# UART_Communication.net
KiCad netlist of a schematic drawn in Altium Designer
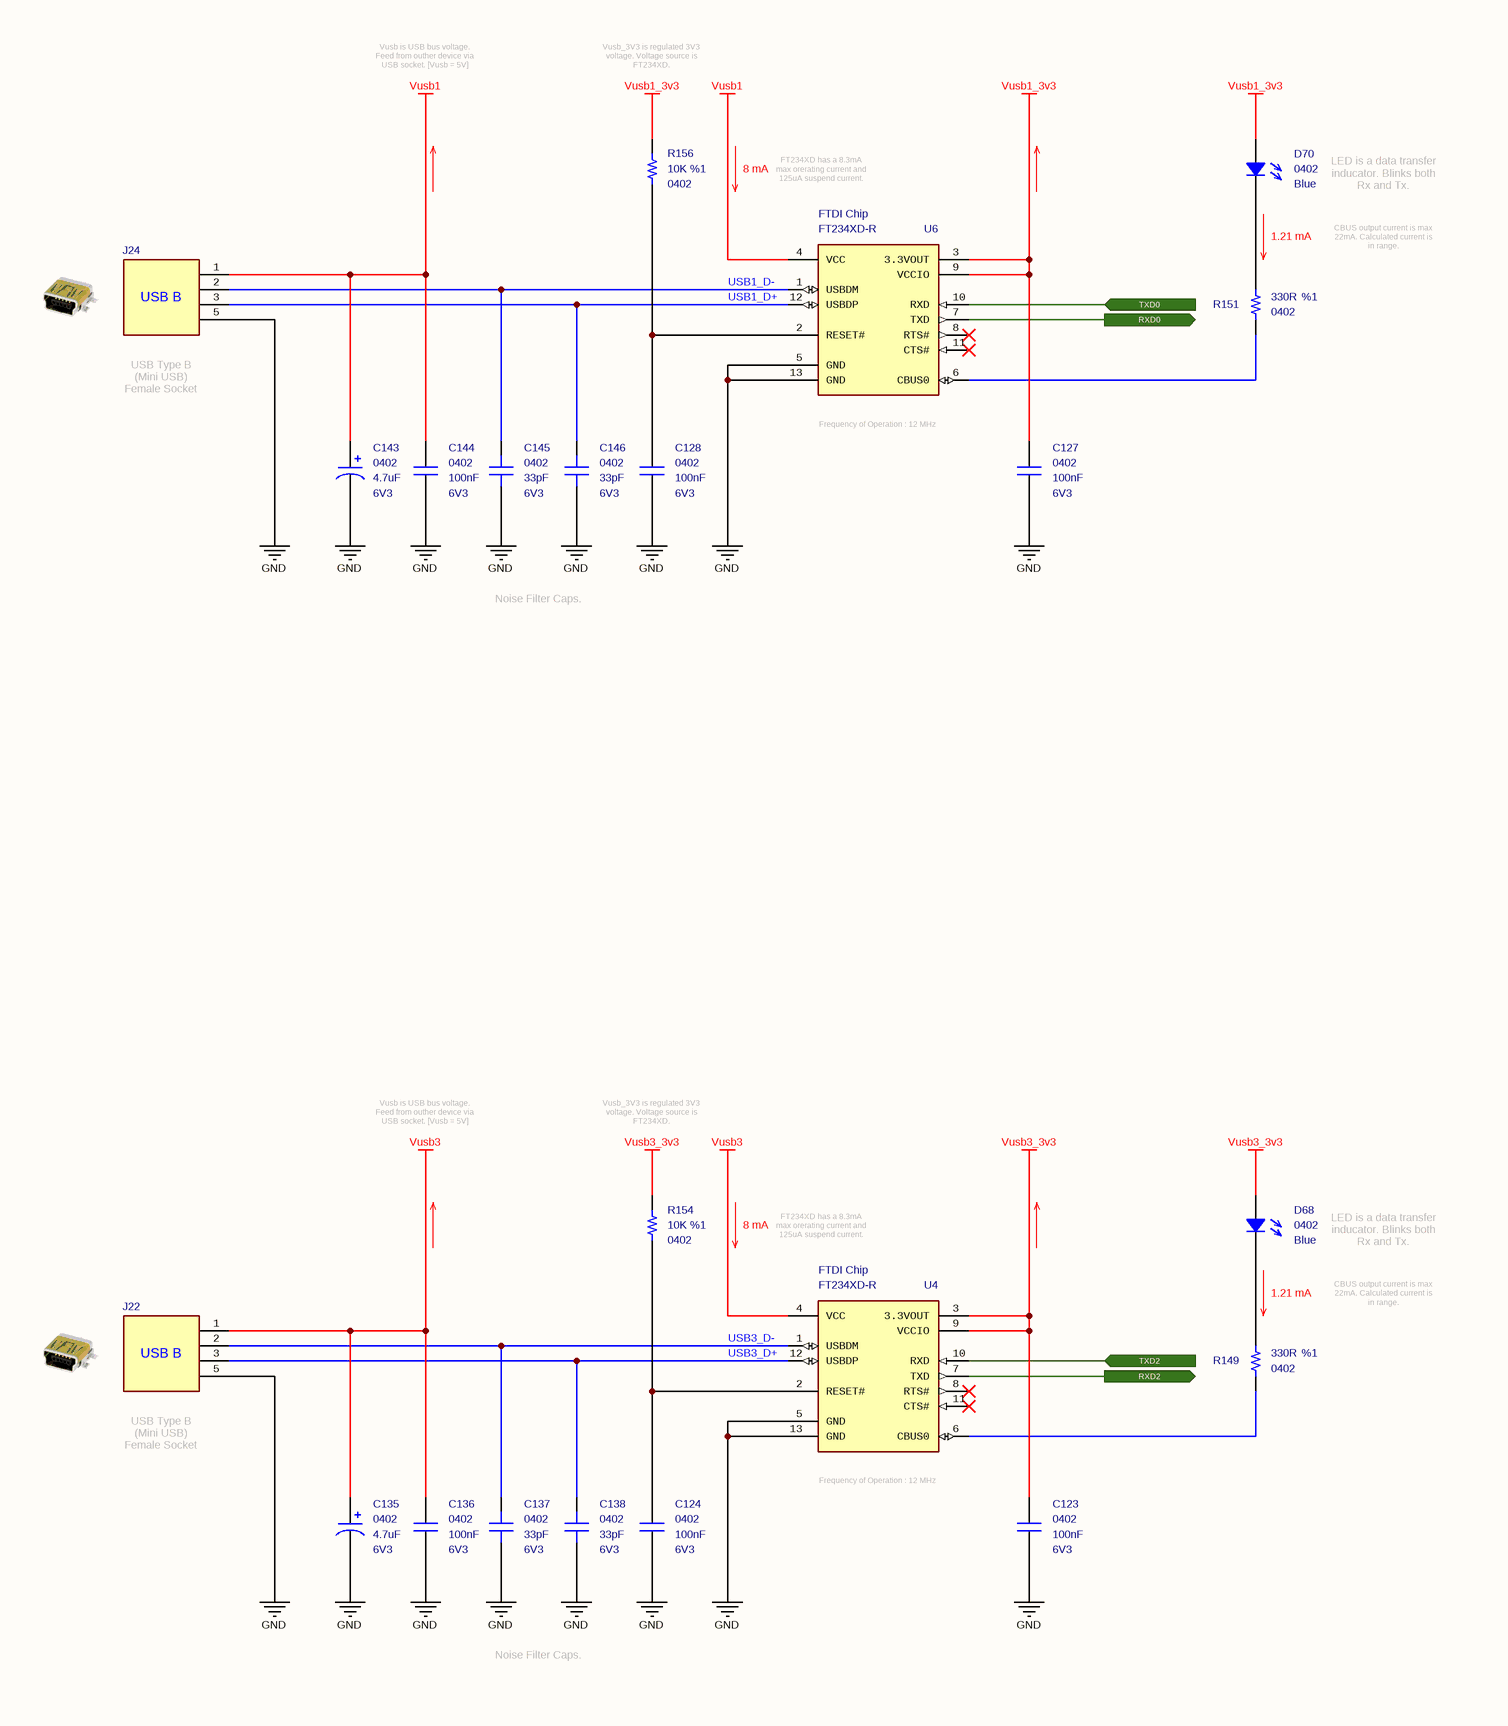
[diagram p0: UART Communication.SchDoc, left]
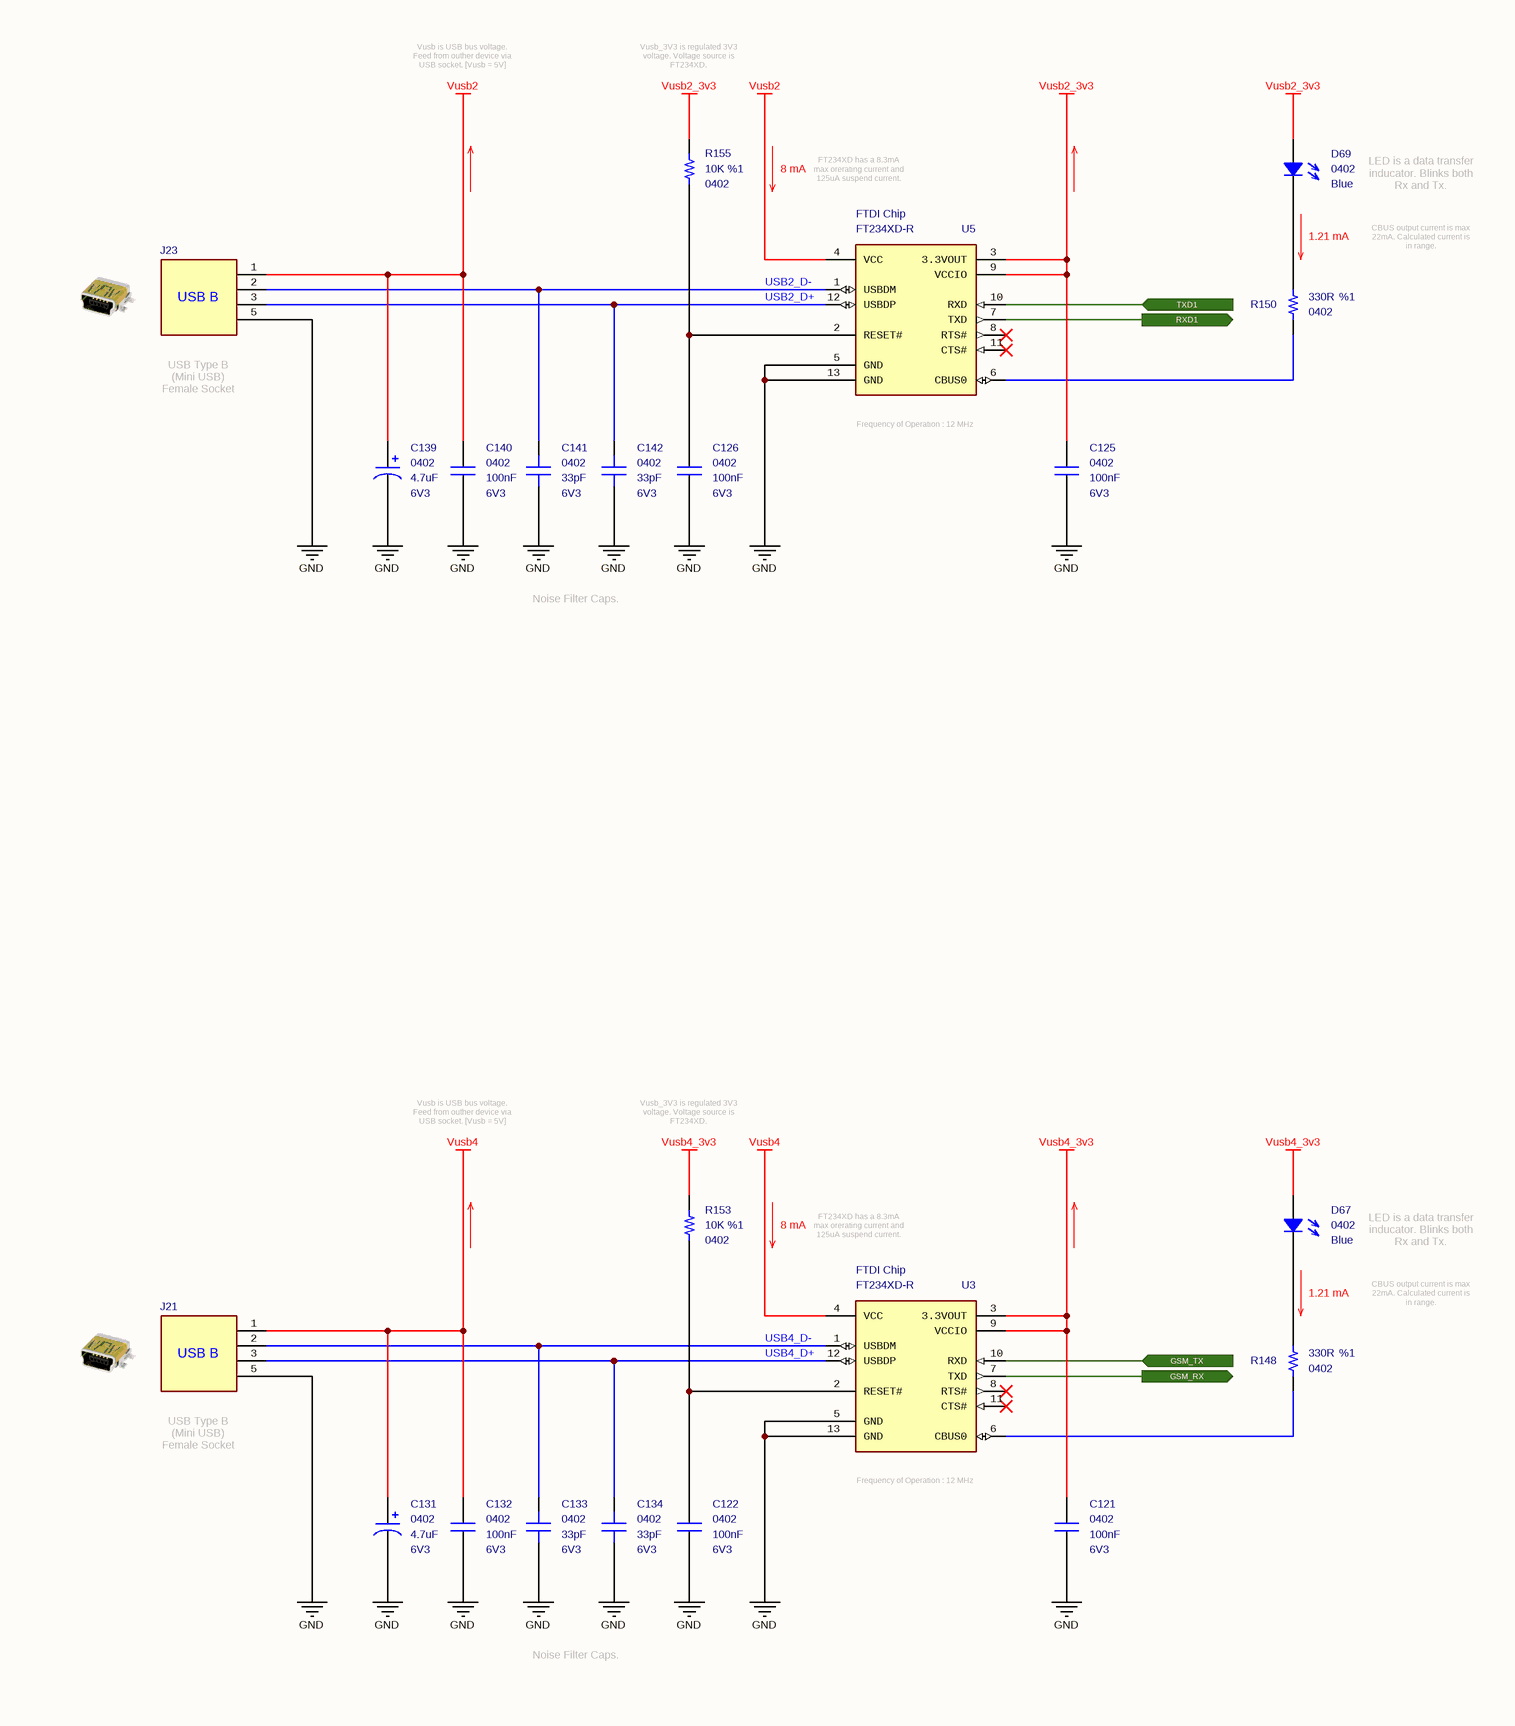
[diagram p1: UART Communication.SchDoc, right]

(export (version "E")
  (design (tool "Eeschema 10.0.6"))
  (components
    (comp (ref "C121")
      (value "100nF")
      (footprint "CAPACITOR_0402")
      (description "Capacitor - 100nF [0402-6V3] (Ceramic)")
      (fields
        (field (name "MANUFACTURER_PART_NUMBER") "04026D104KAT4A")
        (field (name "MOUSER_PART_NUMBER") "581-04026D104KAT4A")
        (field (name "CASE") "0402")
        (field (name "VOLTAGE") "6V3")
      )
      (libsource (lib "Ovoo_Schematic") (part "Capacitor - 100nF [0402-6V3]"))
    )
    (comp (ref "C122")
      (value "100nF")
      (footprint "CAPACITOR_0402")
      (description "Capacitor - 100nF [0402-6V3] (Ceramic)")
      (fields
        (field (name "MANUFACTURER_PART_NUMBER") "04026D104KAT4A")
        (field (name "MOUSER_PART_NUMBER") "581-04026D104KAT4A")
        (field (name "CASE") "0402")
        (field (name "VOLTAGE") "6V3")
      )
      (libsource (lib "Ovoo_Schematic") (part "Capacitor - 100nF [0402-6V3]"))
    )
    (comp (ref "C123")
      (value "100nF")
      (footprint "CAPACITOR_0402")
      (description "Capacitor - 100nF [0402-6V3] (Ceramic)")
      (fields
        (field (name "MANUFACTURER_PART_NUMBER") "04026D104KAT4A")
        (field (name "MOUSER_PART_NUMBER") "581-04026D104KAT4A")
        (field (name "CASE") "0402")
        (field (name "VOLTAGE") "6V3")
      )
      (libsource (lib "Ovoo_Schematic") (part "Capacitor - 100nF [0402-6V3]"))
    )
    (comp (ref "C124")
      (value "100nF")
      (footprint "CAPACITOR_0402")
      (description "Capacitor - 100nF [0402-6V3] (Ceramic)")
      (fields
        (field (name "MANUFACTURER_PART_NUMBER") "04026D104KAT4A")
        (field (name "MOUSER_PART_NUMBER") "581-04026D104KAT4A")
        (field (name "CASE") "0402")
        (field (name "VOLTAGE") "6V3")
      )
      (libsource (lib "Ovoo_Schematic") (part "Capacitor - 100nF [0402-6V3]"))
    )
    (comp (ref "C125")
      (value "100nF")
      (footprint "CAPACITOR_0402")
      (description "Capacitor - 100nF [0402-6V3] (Ceramic)")
      (fields
        (field (name "MANUFACTURER_PART_NUMBER") "04026D104KAT4A")
        (field (name "MOUSER_PART_NUMBER") "581-04026D104KAT4A")
        (field (name "CASE") "0402")
        (field (name "VOLTAGE") "6V3")
      )
      (libsource (lib "Ovoo_Schematic") (part "Capacitor - 100nF [0402-6V3]"))
    )
    (comp (ref "C126")
      (value "100nF")
      (footprint "CAPACITOR_0402")
      (description "Capacitor - 100nF [0402-6V3] (Ceramic)")
      (fields
        (field (name "MANUFACTURER_PART_NUMBER") "04026D104KAT4A")
        (field (name "MOUSER_PART_NUMBER") "581-04026D104KAT4A")
        (field (name "CASE") "0402")
        (field (name "VOLTAGE") "6V3")
      )
      (libsource (lib "Ovoo_Schematic") (part "Capacitor - 100nF [0402-6V3]"))
    )
    (comp (ref "C127")
      (value "100nF")
      (footprint "CAPACITOR_0402")
      (description "Capacitor - 100nF [0402-6V3] (Ceramic)")
      (fields
        (field (name "MANUFACTURER_PART_NUMBER") "04026D104KAT4A")
        (field (name "MOUSER_PART_NUMBER") "581-04026D104KAT4A")
        (field (name "CASE") "0402")
        (field (name "VOLTAGE") "6V3")
      )
      (libsource (lib "Ovoo_Schematic") (part "Capacitor - 100nF [0402-6V3]"))
    )
    (comp (ref "C128")
      (value "100nF")
      (footprint "CAPACITOR_0402")
      (description "Capacitor - 100nF [0402-6V3] (Ceramic)")
      (fields
        (field (name "MANUFACTURER_PART_NUMBER") "04026D104KAT4A")
        (field (name "MOUSER_PART_NUMBER") "581-04026D104KAT4A")
        (field (name "CASE") "0402")
        (field (name "VOLTAGE") "6V3")
      )
      (libsource (lib "Ovoo_Schematic") (part "Capacitor - 100nF [0402-6V3]"))
    )
    (comp (ref "C131")
      (value "4.7uF")
      (footprint "CAPACITOR_0402")
      (description "Capacitor - 4.7uF [0402] (Ceramic)")
      (fields
        (field (name "MANUFACTURER_PART_NUMBER") "C0402C475M9PACTU")
        (field (name "MOUSER_PART_NUMBER") "80-C0402C475M9P")
        (field (name "CASE") "0402")
        (field (name "VOLTAGE") "6V3")
      )
      (libsource (lib "Ovoo_Schematic") (part "Capacitor - 4.7uF [0402-6V3)"))
    )
    (comp (ref "C132")
      (value "100nF")
      (footprint "CAPACITOR_0402")
      (description "Capacitor - 100nF [0402-6V3] (Ceramic)")
      (fields
        (field (name "MANUFACTURER_PART_NUMBER") "04026D104KAT4A")
        (field (name "MOUSER_PART_NUMBER") "581-04026D104KAT4A")
        (field (name "CASE") "0402")
        (field (name "VOLTAGE") "6V3")
      )
      (libsource (lib "Ovoo_Schematic") (part "Capacitor - 100nF [0402-6V3]"))
    )
    (comp (ref "C133")
      (value "33pF")
      (footprint "CAPACITOR_0402")
      (description "Capacitor - 33pF [0402] (Ceramic)")
      (fields
        (field (name "MANUFACTURER_PART_NUMBER") "C0402C330J9RACAUTO")
        (field (name "MOUSER_PART_NUMBER") "80-C0402C330J9RAUTO")
        (field (name "CASE") "0402")
        (field (name "VOLTAGE") "6V3")
      )
      (libsource (lib "Ovoo_Schematic") (part "Capacitor - 33pF [0402-6V3]"))
    )
    (comp (ref "C134")
      (value "33pF")
      (footprint "CAPACITOR_0402")
      (description "Capacitor - 33pF [0402] (Ceramic)")
      (fields
        (field (name "MANUFACTURER_PART_NUMBER") "C0402C330J9RACAUTO")
        (field (name "MOUSER_PART_NUMBER") "80-C0402C330J9RAUTO")
        (field (name "CASE") "0402")
        (field (name "VOLTAGE") "6V3")
      )
      (libsource (lib "Ovoo_Schematic") (part "Capacitor - 33pF [0402-6V3]"))
    )
    (comp (ref "C135")
      (value "4.7uF")
      (footprint "CAPACITOR_0402")
      (description "Capacitor - 4.7uF [0402] (Ceramic)")
      (fields
        (field (name "MANUFACTURER_PART_NUMBER") "C0402C475M9PACTU")
        (field (name "MOUSER_PART_NUMBER") "80-C0402C475M9P")
        (field (name "CASE") "0402")
        (field (name "VOLTAGE") "6V3")
      )
      (libsource (lib "Ovoo_Schematic") (part "Capacitor - 4.7uF [0402-6V3)"))
    )
    (comp (ref "C136")
      (value "100nF")
      (footprint "CAPACITOR_0402")
      (description "Capacitor - 100nF [0402-6V3] (Ceramic)")
      (fields
        (field (name "MANUFACTURER_PART_NUMBER") "04026D104KAT4A")
        (field (name "MOUSER_PART_NUMBER") "581-04026D104KAT4A")
        (field (name "CASE") "0402")
        (field (name "VOLTAGE") "6V3")
      )
      (libsource (lib "Ovoo_Schematic") (part "Capacitor - 100nF [0402-6V3]"))
    )
    (comp (ref "C137")
      (value "33pF")
      (footprint "CAPACITOR_0402")
      (description "Capacitor - 33pF [0402] (Ceramic)")
      (fields
        (field (name "MANUFACTURER_PART_NUMBER") "C0402C330J9RACAUTO")
        (field (name "MOUSER_PART_NUMBER") "80-C0402C330J9RAUTO")
        (field (name "CASE") "0402")
        (field (name "VOLTAGE") "6V3")
      )
      (libsource (lib "Ovoo_Schematic") (part "Capacitor - 33pF [0402-6V3]"))
    )
    (comp (ref "C138")
      (value "33pF")
      (footprint "CAPACITOR_0402")
      (description "Capacitor - 33pF [0402] (Ceramic)")
      (fields
        (field (name "MANUFACTURER_PART_NUMBER") "C0402C330J9RACAUTO")
        (field (name "MOUSER_PART_NUMBER") "80-C0402C330J9RAUTO")
        (field (name "CASE") "0402")
        (field (name "VOLTAGE") "6V3")
      )
      (libsource (lib "Ovoo_Schematic") (part "Capacitor - 33pF [0402-6V3]"))
    )
    (comp (ref "C139")
      (value "4.7uF")
      (footprint "CAPACITOR_0402")
      (description "Capacitor - 4.7uF [0402] (Ceramic)")
      (fields
        (field (name "MANUFACTURER_PART_NUMBER") "C0402C475M9PACTU")
        (field (name "MOUSER_PART_NUMBER") "80-C0402C475M9P")
        (field (name "CASE") "0402")
        (field (name "VOLTAGE") "6V3")
      )
      (libsource (lib "Ovoo_Schematic") (part "Capacitor - 4.7uF [0402-6V3)"))
    )
    (comp (ref "C140")
      (value "100nF")
      (footprint "CAPACITOR_0402")
      (description "Capacitor - 100nF [0402-6V3] (Ceramic)")
      (fields
        (field (name "MANUFACTURER_PART_NUMBER") "04026D104KAT4A")
        (field (name "MOUSER_PART_NUMBER") "581-04026D104KAT4A")
        (field (name "CASE") "0402")
        (field (name "VOLTAGE") "6V3")
      )
      (libsource (lib "Ovoo_Schematic") (part "Capacitor - 100nF [0402-6V3]"))
    )
    (comp (ref "C141")
      (value "33pF")
      (footprint "CAPACITOR_0402")
      (description "Capacitor - 33pF [0402] (Ceramic)")
      (fields
        (field (name "MANUFACTURER_PART_NUMBER") "C0402C330J9RACAUTO")
        (field (name "MOUSER_PART_NUMBER") "80-C0402C330J9RAUTO")
        (field (name "CASE") "0402")
        (field (name "VOLTAGE") "6V3")
      )
      (libsource (lib "Ovoo_Schematic") (part "Capacitor - 33pF [0402-6V3]"))
    )
    (comp (ref "C142")
      (value "33pF")
      (footprint "CAPACITOR_0402")
      (description "Capacitor - 33pF [0402] (Ceramic)")
      (fields
        (field (name "MANUFACTURER_PART_NUMBER") "C0402C330J9RACAUTO")
        (field (name "MOUSER_PART_NUMBER") "80-C0402C330J9RAUTO")
        (field (name "CASE") "0402")
        (field (name "VOLTAGE") "6V3")
      )
      (libsource (lib "Ovoo_Schematic") (part "Capacitor - 33pF [0402-6V3]"))
    )
    (comp (ref "C143")
      (value "4.7uF")
      (footprint "CAPACITOR_0402")
      (description "Capacitor - 4.7uF [0402] (Ceramic)")
      (fields
        (field (name "MANUFACTURER_PART_NUMBER") "C0402C475M9PACTU")
        (field (name "MOUSER_PART_NUMBER") "80-C0402C475M9P")
        (field (name "CASE") "0402")
        (field (name "VOLTAGE") "6V3")
      )
      (libsource (lib "Ovoo_Schematic") (part "Capacitor - 4.7uF [0402-6V3)"))
    )
    (comp (ref "C144")
      (value "100nF")
      (footprint "CAPACITOR_0402")
      (description "Capacitor - 100nF [0402-6V3] (Ceramic)")
      (fields
        (field (name "MANUFACTURER_PART_NUMBER") "04026D104KAT4A")
        (field (name "MOUSER_PART_NUMBER") "581-04026D104KAT4A")
        (field (name "CASE") "0402")
        (field (name "VOLTAGE") "6V3")
      )
      (libsource (lib "Ovoo_Schematic") (part "Capacitor - 100nF [0402-6V3]"))
    )
    (comp (ref "C145")
      (value "33pF")
      (footprint "CAPACITOR_0402")
      (description "Capacitor - 33pF [0402] (Ceramic)")
      (fields
        (field (name "MANUFACTURER_PART_NUMBER") "C0402C330J9RACAUTO")
        (field (name "MOUSER_PART_NUMBER") "80-C0402C330J9RAUTO")
        (field (name "CASE") "0402")
        (field (name "VOLTAGE") "6V3")
      )
      (libsource (lib "Ovoo_Schematic") (part "Capacitor - 33pF [0402-6V3]"))
    )
    (comp (ref "C146")
      (value "33pF")
      (footprint "CAPACITOR_0402")
      (description "Capacitor - 33pF [0402] (Ceramic)")
      (fields
        (field (name "MANUFACTURER_PART_NUMBER") "C0402C330J9RACAUTO")
        (field (name "MOUSER_PART_NUMBER") "80-C0402C330J9RAUTO")
        (field (name "CASE") "0402")
        (field (name "VOLTAGE") "6V3")
      )
      (libsource (lib "Ovoo_Schematic") (part "Capacitor - 33pF [0402-6V3]"))
    )
    (comp (ref "D67")
      (value "SMD LED (Blue)")
      (footprint "LED_0402")
      (description "Standard LEDs - SMD PICOLEDTM;BLUE LED; 25M @ 5MA")
      (fields
        (field (name "MANUFACTURER_PART_NUMBER") "SMLP13BC8TT86")
        (field (name "MOUSER_PART_NUMBER") "755-SMLP13BC8TT86")
        (field (name "CASE") "0402")
        (field (name "COLOR") "Blue")
      )
      (libsource (lib "Ovoo_Schematic") (part "Diode - LED (0402-Blue)"))
    )
    (comp (ref "D68")
      (value "SMD LED (Blue)")
      (footprint "LED_0402")
      (description "Standard LEDs - SMD PICOLEDTM;BLUE LED; 25M @ 5MA")
      (fields
        (field (name "MANUFACTURER_PART_NUMBER") "SMLP13BC8TT86")
        (field (name "MOUSER_PART_NUMBER") "755-SMLP13BC8TT86")
        (field (name "CASE") "0402")
        (field (name "COLOR") "Blue")
      )
      (libsource (lib "Ovoo_Schematic") (part "Diode - LED (0402-Blue)"))
    )
    (comp (ref "D69")
      (value "SMD LED (Blue)")
      (footprint "LED_0402")
      (description "Standard LEDs - SMD PICOLEDTM;BLUE LED; 25M @ 5MA")
      (fields
        (field (name "MANUFACTURER_PART_NUMBER") "SMLP13BC8TT86")
        (field (name "MOUSER_PART_NUMBER") "755-SMLP13BC8TT86")
        (field (name "CASE") "0402")
        (field (name "COLOR") "Blue")
      )
      (libsource (lib "Ovoo_Schematic") (part "Diode - LED (0402-Blue)"))
    )
    (comp (ref "D70")
      (value "SMD LED (Blue)")
      (footprint "LED_0402")
      (description "Standard LEDs - SMD PICOLEDTM;BLUE LED; 25M @ 5MA")
      (fields
        (field (name "MANUFACTURER_PART_NUMBER") "SMLP13BC8TT86")
        (field (name "MOUSER_PART_NUMBER") "755-SMLP13BC8TT86")
        (field (name "CASE") "0402")
        (field (name "COLOR") "Blue")
      )
      (libsource (lib "Ovoo_Schematic") (part "Diode - LED (0402-Blue)"))
    )
    (comp (ref "J21")
      (value "Mini USB Type B Connector")
      (footprint "USB Micro B Female - Vertical")
      (description "USB Connectors MINI B RECEPT RA SMT W/ POST")
      (fields
        (field (name "MANUFACTURER_PART_NUMBER") "105133-0011")
        (field (name "MOUSER_PART_NUMBER") "538-105133-0011")
        (field (name "CONTACT") "5")
      )
      (libsource (lib "Ovoo_Schematic") (part "Connector - Mini USB Female (Vertical)"))
    )
    (comp (ref "J22")
      (value "Mini USB Type B Connector")
      (footprint "USB Micro B Female - Vertical")
      (description "USB Connectors MINI B RECEPT RA SMT W/ POST")
      (fields
        (field (name "MANUFACTURER_PART_NUMBER") "105133-0011")
        (field (name "MOUSER_PART_NUMBER") "538-105133-0011")
        (field (name "CONTACT") "5")
      )
      (libsource (lib "Ovoo_Schematic") (part "Connector - Mini USB Female (Vertical)"))
    )
    (comp (ref "J23")
      (value "Mini USB Type B Connector")
      (footprint "USB Micro B Female - Vertical")
      (description "USB Connectors MINI B RECEPT RA SMT W/ POST")
      (fields
        (field (name "MANUFACTURER_PART_NUMBER") "105133-0011")
        (field (name "MOUSER_PART_NUMBER") "538-105133-0011")
        (field (name "CONTACT") "5")
      )
      (libsource (lib "Ovoo_Schematic") (part "Connector - Mini USB Female (Vertical)"))
    )
    (comp (ref "J24")
      (value "Mini USB Type B Connector")
      (footprint "USB Micro B Female - Vertical")
      (description "USB Connectors MINI B RECEPT RA SMT W/ POST")
      (fields
        (field (name "MANUFACTURER_PART_NUMBER") "105133-0011")
        (field (name "MOUSER_PART_NUMBER") "538-105133-0011")
        (field (name "CONTACT") "5")
      )
      (libsource (lib "Ovoo_Schematic") (part "Connector - Mini USB Female (Vertical)"))
    )
    (comp (ref "R148")
      (value "330R")
      (footprint "RESISTOR_0402")
      (description "Thick Film Resistors - SMD 1/16 W 330 Ohm 1%")
      (fields
        (field (name "MANUFACTURER_PART_NUMBER") "CRCW0402330RFKED")
        (field (name "MOUSER_PART_NUMBER") "71-CRCW0402-330-E3")
        (field (name "TOLERANCE") "%1")
        (field (name "CASE") "0402")
      )
      (libsource (lib "Ovoo_Schematic") (part "Resistor - 330R"))
    )
    (comp (ref "R149")
      (value "330R")
      (footprint "RESISTOR_0402")
      (description "Thick Film Resistors - SMD 1/16 W 330 Ohm 1%")
      (fields
        (field (name "MANUFACTURER_PART_NUMBER") "CRCW0402330RFKED")
        (field (name "MOUSER_PART_NUMBER") "71-CRCW0402-330-E3")
        (field (name "TOLERANCE") "%1")
        (field (name "CASE") "0402")
      )
      (libsource (lib "Ovoo_Schematic") (part "Resistor - 330R"))
    )
    (comp (ref "R150")
      (value "330R")
      (footprint "RESISTOR_0402")
      (description "Thick Film Resistors - SMD 1/16 W 330 Ohm 1%")
      (fields
        (field (name "MANUFACTURER_PART_NUMBER") "CRCW0402330RFKED")
        (field (name "MOUSER_PART_NUMBER") "71-CRCW0402-330-E3")
        (field (name "TOLERANCE") "%1")
        (field (name "CASE") "0402")
      )
      (libsource (lib "Ovoo_Schematic") (part "Resistor - 330R"))
    )
    (comp (ref "R151")
      (value "330R")
      (footprint "RESISTOR_0402")
      (description "Thick Film Resistors - SMD 1/16 W 330 Ohm 1%")
      (fields
        (field (name "MANUFACTURER_PART_NUMBER") "CRCW0402330RFKED")
        (field (name "MOUSER_PART_NUMBER") "71-CRCW0402-330-E3")
        (field (name "TOLERANCE") "%1")
        (field (name "CASE") "0402")
      )
      (libsource (lib "Ovoo_Schematic") (part "Resistor - 330R"))
    )
    (comp (ref "R153")
      (value "10K")
      (footprint "RESISTOR_0402")
      (description "Thick Film Resistors - SMD 1/16 W 10 Kohms 1%")
      (fields
        (field (name "MANUFACTURER_PART_NUMBER") "CRCW040210K0FKED")
        (field (name "MOUSER_PART_NUMBER") "71-CRCW0402-10K-E3")
        (field (name "TOLERANCE") "%1")
        (field (name "CASE") "0402")
      )
      (libsource (lib "Ovoo_Schematic") (part "Resistor - 10K"))
    )
    (comp (ref "R154")
      (value "10K")
      (footprint "RESISTOR_0402")
      (description "Thick Film Resistors - SMD 1/16 W 10 Kohms 1%")
      (fields
        (field (name "MANUFACTURER_PART_NUMBER") "CRCW040210K0FKED")
        (field (name "MOUSER_PART_NUMBER") "71-CRCW0402-10K-E3")
        (field (name "TOLERANCE") "%1")
        (field (name "CASE") "0402")
      )
      (libsource (lib "Ovoo_Schematic") (part "Resistor - 10K"))
    )
    (comp (ref "R155")
      (value "10K")
      (footprint "RESISTOR_0402")
      (description "Thick Film Resistors - SMD 1/16 W 10 Kohms 1%")
      (fields
        (field (name "MANUFACTURER_PART_NUMBER") "CRCW040210K0FKED")
        (field (name "MOUSER_PART_NUMBER") "71-CRCW0402-10K-E3")
        (field (name "TOLERANCE") "%1")
        (field (name "CASE") "0402")
      )
      (libsource (lib "Ovoo_Schematic") (part "Resistor - 10K"))
    )
    (comp (ref "R156")
      (value "10K")
      (footprint "RESISTOR_0402")
      (description "Thick Film Resistors - SMD 1/16 W 10 Kohms 1%")
      (fields
        (field (name "MANUFACTURER_PART_NUMBER") "CRCW040210K0FKED")
        (field (name "MOUSER_PART_NUMBER") "71-CRCW0402-10K-E3")
        (field (name "TOLERANCE") "%1")
        (field (name "CASE") "0402")
      )
      (libsource (lib "Ovoo_Schematic") (part "Resistor - 10K"))
    )
    (comp (ref "U3")
      (value "USB/UART IC")
      (footprint "DFN-12")
      (fields
        (field (name "MOUSER PART NUMBER") "895-FT234XD-R")
        (field (name "MANUFACTURER_PART_NUMBER") "FT234XD-R")
        (field (name "MANUFACTURER_NAME") "FTDI Chip")
      )
      (libsource (lib "Ovoo_Schematic") (part "IC - FT234XD-R"))
    )
    (comp (ref "U4")
      (value "USB/UART IC")
      (footprint "DFN-12")
      (fields
        (field (name "MOUSER PART NUMBER") "895-FT234XD-R")
        (field (name "MANUFACTURER_PART_NUMBER") "FT234XD-R")
        (field (name "MANUFACTURER_NAME") "FTDI Chip")
      )
      (libsource (lib "Ovoo_Schematic") (part "IC - FT234XD-R"))
    )
    (comp (ref "U5")
      (value "USB/UART IC")
      (footprint "DFN-12")
      (fields
        (field (name "MOUSER PART NUMBER") "895-FT234XD-R")
        (field (name "MANUFACTURER_PART_NUMBER") "FT234XD-R")
        (field (name "MANUFACTURER_NAME") "FTDI Chip")
      )
      (libsource (lib "Ovoo_Schematic") (part "IC - FT234XD-R"))
    )
    (comp (ref "U6")
      (value "USB/UART IC")
      (footprint "DFN-12")
      (fields
        (field (name "MOUSER PART NUMBER") "895-FT234XD-R")
        (field (name "MANUFACTURER_PART_NUMBER") "FT234XD-R")
        (field (name "MANUFACTURER_NAME") "FTDI Chip")
      )
      (libsource (lib "Ovoo_Schematic") (part "IC - FT234XD-R"))
    )
  )
  (nets
    (net (code "1") (name "/GSM_RX") (class "Default")
      (node (ref "U3") (pin "7") (pinfunction "TXD_7") (pintype "output"))
    )
    (net (code "2") (name "/GSM_TX") (class "Default")
      (node (ref "U3") (pin "10") (pinfunction "RXD_10") (pintype "input"))
    )
    (net (code "3") (name "/RXD0") (class "Default")
      (node (ref "U6") (pin "7") (pinfunction "TXD_7") (pintype "output"))
    )
    (net (code "4") (name "/RXD1") (class "Default")
      (node (ref "U5") (pin "7") (pinfunction "TXD_7") (pintype "output"))
    )
    (net (code "5") (name "/RXD2") (class "Default")
      (node (ref "U4") (pin "7") (pinfunction "TXD_7") (pintype "output"))
    )
    (net (code "6") (name "/TXD0") (class "Default")
      (node (ref "U6") (pin "10") (pinfunction "RXD_10") (pintype "input"))
    )
    (net (code "7") (name "/TXD1") (class "Default")
      (node (ref "U5") (pin "10") (pinfunction "RXD_10") (pintype "input"))
    )
    (net (code "8") (name "/TXD2") (class "Default")
      (node (ref "U4") (pin "10") (pinfunction "RXD_10") (pintype "input"))
    )
    (net (code "9") (name "/USB1_D+") (class "Default")
      (node (ref "C146") (pin "1") (pinfunction "1_1") (pintype "passive"))
      (node (ref "J24") (pin "3") (pinfunction "D+_3") (pintype "passive"))
      (node (ref "U6") (pin "12") (pinfunction "USBDP_12") (pintype "bidirectional"))
    )
    (net (code "10") (name "/USB1_D-") (class "Default")
      (node (ref "C145") (pin "1") (pinfunction "1_1") (pintype "passive"))
      (node (ref "J24") (pin "2") (pinfunction "D-_2") (pintype "passive"))
      (node (ref "U6") (pin "1") (pinfunction "USBDM_1") (pintype "bidirectional"))
    )
    (net (code "11") (name "/USB2_D+") (class "Default")
      (node (ref "C142") (pin "1") (pinfunction "1_1") (pintype "passive"))
      (node (ref "J23") (pin "3") (pinfunction "D+_3") (pintype "passive"))
      (node (ref "U5") (pin "12") (pinfunction "USBDP_12") (pintype "bidirectional"))
    )
    (net (code "12") (name "/USB2_D-") (class "Default")
      (node (ref "C141") (pin "1") (pinfunction "1_1") (pintype "passive"))
      (node (ref "J23") (pin "2") (pinfunction "D-_2") (pintype "passive"))
      (node (ref "U5") (pin "1") (pinfunction "USBDM_1") (pintype "bidirectional"))
    )
    (net (code "13") (name "/USB3_D+") (class "Default")
      (node (ref "C138") (pin "1") (pinfunction "1_1") (pintype "passive"))
      (node (ref "J22") (pin "3") (pinfunction "D+_3") (pintype "passive"))
      (node (ref "U4") (pin "12") (pinfunction "USBDP_12") (pintype "bidirectional"))
    )
    (net (code "14") (name "/USB3_D-") (class "Default")
      (node (ref "C137") (pin "1") (pinfunction "1_1") (pintype "passive"))
      (node (ref "J22") (pin "2") (pinfunction "D-_2") (pintype "passive"))
      (node (ref "U4") (pin "1") (pinfunction "USBDM_1") (pintype "bidirectional"))
    )
    (net (code "15") (name "/USB4_D+") (class "Default")
      (node (ref "C134") (pin "1") (pinfunction "1_1") (pintype "passive"))
      (node (ref "J21") (pin "3") (pinfunction "D+_3") (pintype "passive"))
      (node (ref "U3") (pin "12") (pinfunction "USBDP_12") (pintype "bidirectional"))
    )
    (net (code "16") (name "/USB4_D-") (class "Default")
      (node (ref "C133") (pin "1") (pinfunction "1_1") (pintype "passive"))
      (node (ref "J21") (pin "2") (pinfunction "D-_2") (pintype "passive"))
      (node (ref "U3") (pin "1") (pinfunction "USBDM_1") (pintype "bidirectional"))
    )
    (net (code "17") (name "GND") (class "Default")
      (node (ref "C121") (pin "2") (pinfunction "2_2") (pintype "passive"))
      (node (ref "C122") (pin "2") (pinfunction "2_2") (pintype "passive"))
      (node (ref "C123") (pin "2") (pinfunction "2_2") (pintype "passive"))
      (node (ref "C124") (pin "2") (pinfunction "2_2") (pintype "passive"))
      (node (ref "C125") (pin "2") (pinfunction "2_2") (pintype "passive"))
      (node (ref "C126") (pin "2") (pinfunction "2_2") (pintype "passive"))
      (node (ref "C127") (pin "2") (pinfunction "2_2") (pintype "passive"))
      (node (ref "C128") (pin "2") (pinfunction "2_2") (pintype "passive"))
      (node (ref "C131") (pin "2") (pinfunction "2_2") (pintype "passive"))
      (node (ref "C132") (pin "1") (pinfunction "1_1") (pintype "passive"))
      (node (ref "C133") (pin "2") (pinfunction "2_2") (pintype "passive"))
      (node (ref "C134") (pin "2") (pinfunction "2_2") (pintype "passive"))
      (node (ref "C135") (pin "2") (pinfunction "2_2") (pintype "passive"))
      (node (ref "C136") (pin "1") (pinfunction "1_1") (pintype "passive"))
      (node (ref "C137") (pin "2") (pinfunction "2_2") (pintype "passive"))
      (node (ref "C138") (pin "2") (pinfunction "2_2") (pintype "passive"))
      (node (ref "C139") (pin "2") (pinfunction "2_2") (pintype "passive"))
      (node (ref "C140") (pin "1") (pinfunction "1_1") (pintype "passive"))
      (node (ref "C141") (pin "2") (pinfunction "2_2") (pintype "passive"))
      (node (ref "C142") (pin "2") (pinfunction "2_2") (pintype "passive"))
      (node (ref "C143") (pin "2") (pinfunction "2_2") (pintype "passive"))
      (node (ref "C144") (pin "1") (pinfunction "1_1") (pintype "passive"))
      (node (ref "C145") (pin "2") (pinfunction "2_2") (pintype "passive"))
      (node (ref "C146") (pin "2") (pinfunction "2_2") (pintype "passive"))
      (node (ref "J21") (pin "5") (pinfunction "GND_5") (pintype "passive"))
      (node (ref "J22") (pin "5") (pinfunction "GND_5") (pintype "passive"))
      (node (ref "J23") (pin "5") (pinfunction "GND_5") (pintype "passive"))
      (node (ref "J24") (pin "5") (pinfunction "GND_5") (pintype "passive"))
      (node (ref "U3") (pin "13") (pinfunction "GND_13") (pintype "power_in"))
      (node (ref "U3") (pin "5") (pinfunction "GND_5") (pintype "power_in"))
      (node (ref "U4") (pin "13") (pinfunction "GND_13") (pintype "power_in"))
      (node (ref "U4") (pin "5") (pinfunction "GND_5") (pintype "power_in"))
      (node (ref "U5") (pin "13") (pinfunction "GND_13") (pintype "power_in"))
      (node (ref "U5") (pin "5") (pinfunction "GND_5") (pintype "power_in"))
      (node (ref "U6") (pin "13") (pinfunction "GND_13") (pintype "power_in"))
      (node (ref "U6") (pin "5") (pinfunction "GND_5") (pintype "power_in"))
    )
    (net (code "18") (name "Net-(D67-Pad1)") (class "Default")
      (node (ref "D67") (pin "1") (pinfunction "1_1") (pintype "passive"))
      (node (ref "R148") (pin "1") (pinfunction "1_1") (pintype "passive"))
    )
    (net (code "19") (name "Net-(D68-Pad1)") (class "Default")
      (node (ref "D68") (pin "1") (pinfunction "1_1") (pintype "passive"))
      (node (ref "R149") (pin "1") (pinfunction "1_1") (pintype "passive"))
    )
    (net (code "20") (name "Net-(D69-Pad1)") (class "Default")
      (node (ref "D69") (pin "1") (pinfunction "1_1") (pintype "passive"))
      (node (ref "R150") (pin "1") (pinfunction "1_1") (pintype "passive"))
    )
    (net (code "21") (name "Net-(D70-Pad1)") (class "Default")
      (node (ref "D70") (pin "1") (pinfunction "1_1") (pintype "passive"))
      (node (ref "R151") (pin "1") (pinfunction "1_1") (pintype "passive"))
    )
    (net (code "22") (name "Net-(U3-CBUS0)") (class "Default")
      (node (ref "R148") (pin "2") (pinfunction "2_2") (pintype "passive"))
      (node (ref "U3") (pin "6") (pinfunction "CBUS0_6") (pintype "bidirectional"))
    )
    (net (code "23") (name "Net-(U3-RESET#)") (class "Default")
      (node (ref "C122") (pin "1") (pinfunction "1_1") (pintype "passive"))
      (node (ref "R153") (pin "1") (pinfunction "1_1") (pintype "passive"))
      (node (ref "U3") (pin "2") (pinfunction "RESET#_2") (pintype "passive"))
    )
    (net (code "24") (name "Net-(U4-CBUS0)") (class "Default")
      (node (ref "R149") (pin "2") (pinfunction "2_2") (pintype "passive"))
      (node (ref "U4") (pin "6") (pinfunction "CBUS0_6") (pintype "bidirectional"))
    )
    (net (code "25") (name "Net-(U4-RESET#)") (class "Default")
      (node (ref "C124") (pin "1") (pinfunction "1_1") (pintype "passive"))
      (node (ref "R154") (pin "1") (pinfunction "1_1") (pintype "passive"))
      (node (ref "U4") (pin "2") (pinfunction "RESET#_2") (pintype "passive"))
    )
    (net (code "26") (name "Net-(U5-CBUS0)") (class "Default")
      (node (ref "R150") (pin "2") (pinfunction "2_2") (pintype "passive"))
      (node (ref "U5") (pin "6") (pinfunction "CBUS0_6") (pintype "bidirectional"))
    )
    (net (code "27") (name "Net-(U5-RESET#)") (class "Default")
      (node (ref "C126") (pin "1") (pinfunction "1_1") (pintype "passive"))
      (node (ref "R155") (pin "1") (pinfunction "1_1") (pintype "passive"))
      (node (ref "U5") (pin "2") (pinfunction "RESET#_2") (pintype "passive"))
    )
    (net (code "28") (name "Net-(U6-CBUS0)") (class "Default")
      (node (ref "R151") (pin "2") (pinfunction "2_2") (pintype "passive"))
      (node (ref "U6") (pin "6") (pinfunction "CBUS0_6") (pintype "bidirectional"))
    )
    (net (code "29") (name "Net-(U6-RESET#)") (class "Default")
      (node (ref "C128") (pin "1") (pinfunction "1_1") (pintype "passive"))
      (node (ref "R156") (pin "1") (pinfunction "1_1") (pintype "passive"))
      (node (ref "U6") (pin "2") (pinfunction "RESET#_2") (pintype "passive"))
    )
    (net (code "30") (name "Vusb1") (class "Default")
      (node (ref "C143") (pin "1") (pinfunction "1_1") (pintype "passive"))
      (node (ref "C144") (pin "2") (pinfunction "2_2") (pintype "passive"))
      (node (ref "J24") (pin "1") (pinfunction "Vbus_1") (pintype "passive"))
      (node (ref "U6") (pin "4") (pinfunction "VCC_4") (pintype "power_in"))
    )
    (net (code "31") (name "Vusb1_3v3") (class "Default")
      (node (ref "C127") (pin "1") (pinfunction "1_1") (pintype "passive"))
      (node (ref "D70") (pin "2") (pinfunction "2_2") (pintype "passive"))
      (node (ref "R156") (pin "2") (pinfunction "2_2") (pintype "passive"))
      (node (ref "U6") (pin "3") (pinfunction "3.3VOUT_3") (pintype "power_in"))
      (node (ref "U6") (pin "9") (pinfunction "VCCIO_9") (pintype "power_in"))
    )
    (net (code "32") (name "Vusb2") (class "Default")
      (node (ref "C139") (pin "1") (pinfunction "1_1") (pintype "passive"))
      (node (ref "C140") (pin "2") (pinfunction "2_2") (pintype "passive"))
      (node (ref "J23") (pin "1") (pinfunction "Vbus_1") (pintype "passive"))
      (node (ref "U5") (pin "4") (pinfunction "VCC_4") (pintype "power_in"))
    )
    (net (code "33") (name "Vusb2_3v3") (class "Default")
      (node (ref "C125") (pin "1") (pinfunction "1_1") (pintype "passive"))
      (node (ref "D69") (pin "2") (pinfunction "2_2") (pintype "passive"))
      (node (ref "R155") (pin "2") (pinfunction "2_2") (pintype "passive"))
      (node (ref "U5") (pin "3") (pinfunction "3.3VOUT_3") (pintype "power_in"))
      (node (ref "U5") (pin "9") (pinfunction "VCCIO_9") (pintype "power_in"))
    )
    (net (code "34") (name "Vusb3") (class "Default")
      (node (ref "C135") (pin "1") (pinfunction "1_1") (pintype "passive"))
      (node (ref "C136") (pin "2") (pinfunction "2_2") (pintype "passive"))
      (node (ref "J22") (pin "1") (pinfunction "Vbus_1") (pintype "passive"))
      (node (ref "U4") (pin "4") (pinfunction "VCC_4") (pintype "power_in"))
    )
    (net (code "35") (name "Vusb3_3v3") (class "Default")
      (node (ref "C123") (pin "1") (pinfunction "1_1") (pintype "passive"))
      (node (ref "D68") (pin "2") (pinfunction "2_2") (pintype "passive"))
      (node (ref "R154") (pin "2") (pinfunction "2_2") (pintype "passive"))
      (node (ref "U4") (pin "3") (pinfunction "3.3VOUT_3") (pintype "power_in"))
      (node (ref "U4") (pin "9") (pinfunction "VCCIO_9") (pintype "power_in"))
    )
    (net (code "36") (name "Vusb4") (class "Default")
      (node (ref "C131") (pin "1") (pinfunction "1_1") (pintype "passive"))
      (node (ref "C132") (pin "2") (pinfunction "2_2") (pintype "passive"))
      (node (ref "J21") (pin "1") (pinfunction "Vbus_1") (pintype "passive"))
      (node (ref "U3") (pin "4") (pinfunction "VCC_4") (pintype "power_in"))
    )
    (net (code "37") (name "Vusb4_3v3") (class "Default")
      (node (ref "C121") (pin "1") (pinfunction "1_1") (pintype "passive"))
      (node (ref "D67") (pin "2") (pinfunction "2_2") (pintype "passive"))
      (node (ref "R153") (pin "2") (pinfunction "2_2") (pintype "passive"))
      (node (ref "U3") (pin "3") (pinfunction "3.3VOUT_3") (pintype "power_in"))
      (node (ref "U3") (pin "9") (pinfunction "VCCIO_9") (pintype "power_in"))
    )
    (net (code "38") (name "unconnected-(U3-CTS#-Pad11)") (class "Default")
      (node (ref "U3") (pin "11") (pinfunction "CTS#_11") (pintype "input+no_connect"))
    )
    (net (code "39") (name "unconnected-(U3-RTS#-Pad8)") (class "Default")
      (node (ref "U3") (pin "8") (pinfunction "RTS#_8") (pintype "output+no_connect"))
    )
    (net (code "40") (name "unconnected-(U4-CTS#-Pad11)") (class "Default")
      (node (ref "U4") (pin "11") (pinfunction "CTS#_11") (pintype "input+no_connect"))
    )
    (net (code "41") (name "unconnected-(U4-RTS#-Pad8)") (class "Default")
      (node (ref "U4") (pin "8") (pinfunction "RTS#_8") (pintype "output+no_connect"))
    )
    (net (code "42") (name "unconnected-(U5-CTS#-Pad11)") (class "Default")
      (node (ref "U5") (pin "11") (pinfunction "CTS#_11") (pintype "input+no_connect"))
    )
    (net (code "43") (name "unconnected-(U5-RTS#-Pad8)") (class "Default")
      (node (ref "U5") (pin "8") (pinfunction "RTS#_8") (pintype "output+no_connect"))
    )
    (net (code "44") (name "unconnected-(U6-CTS#-Pad11)") (class "Default")
      (node (ref "U6") (pin "11") (pinfunction "CTS#_11") (pintype "input+no_connect"))
    )
    (net (code "45") (name "unconnected-(U6-RTS#-Pad8)") (class "Default")
      (node (ref "U6") (pin "8") (pinfunction "RTS#_8") (pintype "output+no_connect"))
    )
  )
)
